# USB.net
KiCad netlist of a schematic drawn in Altium Designer
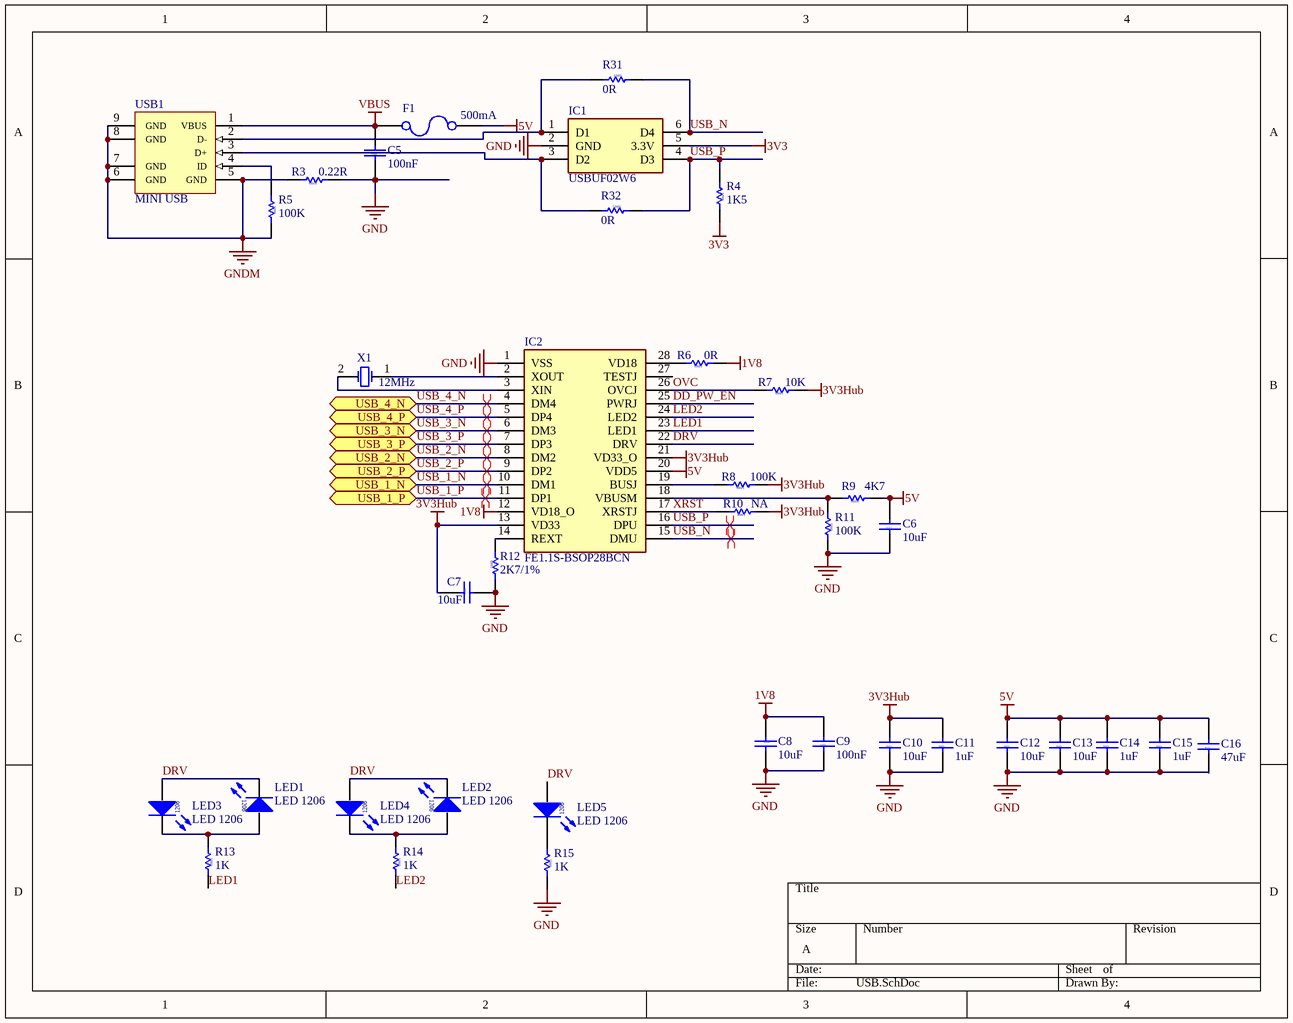
[diagram p0: USB.SchDoc]

(export (version "E")
  (design (tool "Eeschema 10.0.6"))
  (components
    (comp (ref "C5")
      (value "100nF")
      (footprint "RES 0805")
      (libsource (lib "Full lib F.kh-V2") (part "CAP 0805"))
    )
    (comp (ref "C6")
      (value "10uF")
      (footprint "Res 1206")
      (libsource (lib "Full lib F.kh-V2") (part "CAP 1206"))
    )
    (comp (ref "C7")
      (value "10uF")
      (footprint "Res 1206")
      (libsource (lib "Full lib F.kh-V2") (part "CAP 1206"))
    )
    (comp (ref "C8")
      (value "10uF")
      (footprint "Res 1206")
      (libsource (lib "Full lib F.kh-V2") (part "CAP 1206"))
    )
    (comp (ref "C9")
      (value "100nF")
      (footprint "RES 0805")
      (libsource (lib "Full lib F.kh-V2") (part "CAP 0805"))
    )
    (comp (ref "C10")
      (value "10uF")
      (footprint "Res 1206")
      (libsource (lib "Full lib F.kh-V2") (part "CAP 1206"))
    )
    (comp (ref "C11")
      (value "1uF")
      (footprint "Res 1206")
      (libsource (lib "Full lib F.kh-V2") (part "CAP 1206"))
    )
    (comp (ref "C12")
      (value "10uF")
      (footprint "Res 1206")
      (libsource (lib "Full lib F.kh-V2") (part "CAP 1206"))
    )
    (comp (ref "C13")
      (value "10uF")
      (footprint "Res 1206")
      (libsource (lib "Full lib F.kh-V2") (part "CAP 1206"))
    )
    (comp (ref "C14")
      (value "1uF")
      (footprint "Res 1206")
      (libsource (lib "Full lib F.kh-V2") (part "CAP 1206"))
    )
    (comp (ref "C15")
      (value "1uF")
      (footprint "Res 1206")
      (libsource (lib "Full lib F.kh-V2") (part "CAP 1206"))
    )
    (comp (ref "C16")
      (value "47uF")
      (footprint "Res 1206")
      (libsource (lib "Full lib F.kh-V2") (part "CAP 1206"))
    )
    (comp (ref "F1")
      (value "500mA")
      (footprint "Res 1206")
      (libsource (lib "Full lib F.kh-V2") (part "FUSE 1206"))
    )
    (comp (ref "IC1")
      (value "USBUF02W6")
      (footprint "SamacSys:SOT65P210X110-6N")
      (description "Integrated Circuit")
      (fields (field (name "MOUSER PART NUMBER") "511-USBUF02W6"))
      (libsource (lib "*") (part "USBUF02W6"))
    )
    (comp (ref "IC2")
      (value "FE1.1S-BSOP28BCN")
      (footprint "SamacSys:SOP64P600X175-28N")
      (description "Integrated Circuit")
      (libsource (lib "*") (part "FE1.1S-BSOP28BCN"))
    )
    (comp (ref "LED1")
      (value "LED 1206")
      (footprint "LED 1206")
      (libsource (lib "Full lib F.kh-V2") (part "LED 1206"))
    )
    (comp (ref "LED2")
      (value "LED 1206")
      (footprint "LED 1206")
      (libsource (lib "Full lib F.kh-V2") (part "LED 1206"))
    )
    (comp (ref "LED3")
      (value "LED 1206")
      (footprint "LED 1206")
      (libsource (lib "Full lib F.kh-V2") (part "LED 1206"))
    )
    (comp (ref "LED4")
      (value "LED 1206")
      (footprint "LED 1206")
      (libsource (lib "Full lib F.kh-V2") (part "LED 1206"))
    )
    (comp (ref "LED5")
      (value "LED 1206")
      (footprint "LED 1206")
      (libsource (lib "Full lib F.kh-V2") (part "LED 1206"))
    )
    (comp (ref "R3")
      (value "0.22R")
      (footprint "RES 0805")
      (libsource (lib "Full lib F.kh-V2") (part "RES 0805"))
    )
    (comp (ref "R4")
      (value "1K5")
      (footprint "RES 0805")
      (libsource (lib "Full lib F.kh-V2") (part "RES 0805"))
    )
    (comp (ref "R5")
      (value "100K")
      (footprint "RES 0805")
      (libsource (lib "Full lib F.kh-V2") (part "RES 0805"))
    )
    (comp (ref "R6")
      (value "0R")
      (footprint "RES 0805")
      (libsource (lib "Full lib F.kh-V2") (part "RES 0805"))
    )
    (comp (ref "R7")
      (value "10K")
      (footprint "RES 0805")
      (libsource (lib "Full lib F.kh-V2") (part "RES 0805"))
    )
    (comp (ref "R8")
      (value "100K")
      (footprint "RES 0805")
      (libsource (lib "Full lib F.kh-V2") (part "RES 0805"))
    )
    (comp (ref "R9")
      (value "4K7")
      (footprint "RES 0805")
      (libsource (lib "Full lib F.kh-V2") (part "RES 0805"))
    )
    (comp (ref "R10")
      (value "NA")
      (footprint "RES 0805")
      (description "100K")
      (libsource (lib "Full lib F.kh-V2") (part "RES 0805"))
    )
    (comp (ref "R11")
      (value "100K")
      (footprint "RES 0805")
      (libsource (lib "Full lib F.kh-V2") (part "RES 0805"))
    )
    (comp (ref "R12")
      (value "2K7/1%")
      (footprint "RES 0805")
      (libsource (lib "Full lib F.kh-V2") (part "RES 0805"))
    )
    (comp (ref "R13")
      (value "1K")
      (footprint "RES 0805")
      (libsource (lib "Full lib F.kh-V2") (part "RES 0805"))
    )
    (comp (ref "R14")
      (value "1K")
      (footprint "RES 0805")
      (libsource (lib "Full lib F.kh-V2") (part "RES 0805"))
    )
    (comp (ref "R15")
      (value "1K")
      (footprint "RES 0805")
      (libsource (lib "Full lib F.kh-V2") (part "RES 0805"))
    )
    (comp (ref "R31")
      (value "0R")
      (footprint "RES 0805")
      (libsource (lib "Full lib F.kh-V2") (part "RES 0805"))
    )
    (comp (ref "R32")
      (value "0R")
      (footprint "RES 0805")
      (libsource (lib "Full lib F.kh-V2") (part "RES 0805"))
    )
    (comp (ref "USB1")
      (value "MINI USB")
      (footprint "USB MINI DIP")
      (libsource (lib "Full lib F.kh-V2") (part "USB MINI DIP"))
    )
    (comp (ref "X1")
      (value "12MHz")
      (footprint "XTAL - SMD")
      (libsource (lib "Full lib F.kh-V2") (part "XTAL - SMD"))
    )
  )
  (nets
    (net (code "1") (name "/DD_PW_EN") (class "Default")
      (node (ref "IC2") (pin "25") (pinfunction "PWRJ_25") (pintype "passive"))
    )
    (net (code "2") (name "/DRV") (class "Default")
      (node (ref "IC2") (pin "22") (pinfunction "DRV_22") (pintype "passive"))
      (node (ref "LED1") (pin "2") (pinfunction "K_2") (pintype "passive"))
      (node (ref "LED2") (pin "2") (pinfunction "K_2") (pintype "passive"))
      (node (ref "LED3") (pin "1") (pinfunction "A_1") (pintype "passive"))
      (node (ref "LED4") (pin "1") (pinfunction "A_1") (pintype "passive"))
      (node (ref "LED5") (pin "1") (pinfunction "A_1") (pintype "passive"))
    )
    (net (code "3") (name "/LED1") (class "Default")
      (node (ref "IC2") (pin "23") (pinfunction "LED1_23") (pintype "passive"))
      (node (ref "R13") (pin "2") (pinfunction "2_2") (pintype "passive"))
    )
    (net (code "4") (name "/LED2") (class "Default")
      (node (ref "IC2") (pin "24") (pinfunction "LED2_24") (pintype "passive"))
      (node (ref "R14") (pin "2") (pinfunction "2_2") (pintype "passive"))
    )
    (net (code "5") (name "/OVC") (class "Default")
      (node (ref "IC2") (pin "26") (pinfunction "OVCJ_26") (pintype "passive"))
      (node (ref "R7") (pin "2") (pinfunction "2_2") (pintype "passive"))
    )
    (net (code "6") (name "/USB_1_N") (class "Default")
      (node (ref "IC2") (pin "10") (pinfunction "DM1_10") (pintype "passive"))
    )
    (net (code "7") (name "/USB_1_P") (class "Default")
      (node (ref "IC2") (pin "11") (pinfunction "DP1_11") (pintype "passive"))
    )
    (net (code "8") (name "/USB_2_N") (class "Default")
      (node (ref "IC2") (pin "8") (pinfunction "DM2_8") (pintype "passive"))
    )
    (net (code "9") (name "/USB_2_P") (class "Default")
      (node (ref "IC2") (pin "9") (pinfunction "DP2_9") (pintype "passive"))
    )
    (net (code "10") (name "/USB_3_N") (class "Default")
      (node (ref "IC2") (pin "6") (pinfunction "DM3_6") (pintype "passive"))
    )
    (net (code "11") (name "/USB_3_P") (class "Default")
      (node (ref "IC2") (pin "7") (pinfunction "DP3_7") (pintype "passive"))
    )
    (net (code "12") (name "/USB_4_N") (class "Default")
      (node (ref "IC2") (pin "4") (pinfunction "DM4_4") (pintype "passive"))
    )
    (net (code "13") (name "/USB_4_P") (class "Default")
      (node (ref "IC2") (pin "5") (pinfunction "DP4_5") (pintype "passive"))
    )
    (net (code "14") (name "/USB_N") (class "Default")
      (node (ref "IC1") (pin "6") (pinfunction "D4_6") (pintype "passive"))
      (node (ref "IC2") (pin "15") (pinfunction "DMU_15") (pintype "passive"))
      (node (ref "R31") (pin "2") (pinfunction "2_2") (pintype "passive"))
    )
    (net (code "15") (name "/USB_P") (class "Default")
      (node (ref "IC1") (pin "4") (pinfunction "D3_4") (pintype "passive"))
      (node (ref "IC2") (pin "16") (pinfunction "DPU_16") (pintype "passive"))
      (node (ref "R32") (pin "2") (pinfunction "2_2") (pintype "passive"))
      (node (ref "R4") (pin "1") (pinfunction "1_1") (pintype "passive"))
    )
    (net (code "16") (name "/XRST") (class "Default")
      (node (ref "IC2") (pin "17") (pinfunction "XRSTJ_17") (pintype "passive"))
      (node (ref "R10") (pin "2") (pinfunction "2_2") (pintype "passive"))
    )
    (net (code "17") (name "1V8") (class "Default")
      (node (ref "C8") (pin "1") (pinfunction "1_1") (pintype "passive"))
      (node (ref "C9") (pin "2") (pinfunction "2_2") (pintype "passive"))
      (node (ref "IC2") (pin "12") (pinfunction "VD18_O_12") (pintype "passive"))
      (node (ref "R6") (pin "1") (pinfunction "1_1") (pintype "passive"))
    )
    (net (code "18") (name "3V3") (class "Default")
      (node (ref "IC1") (pin "5") (pinfunction "3.3V_5") (pintype "passive"))
      (node (ref "R4") (pin "2") (pinfunction "2_2") (pintype "passive"))
    )
    (net (code "19") (name "3V3Hub") (class "Default")
      (node (ref "C10") (pin "2") (pinfunction "2_2") (pintype "passive"))
      (node (ref "C11") (pin "2") (pinfunction "2_2") (pintype "passive"))
      (node (ref "C7") (pin "1") (pinfunction "1_1") (pintype "passive"))
      (node (ref "IC2") (pin "13") (pinfunction "VD33_13") (pintype "passive"))
      (node (ref "IC2") (pin "21") (pinfunction "VD33_O_21") (pintype "passive"))
      (node (ref "R10") (pin "1") (pinfunction "1_1") (pintype "passive"))
      (node (ref "R7") (pin "1") (pinfunction "1_1") (pintype "passive"))
      (node (ref "R8") (pin "1") (pinfunction "1_1") (pintype "passive"))
    )
    (net (code "20") (name "5V") (class "Default")
      (node (ref "C12") (pin "2") (pinfunction "2_2") (pintype "passive"))
      (node (ref "C13") (pin "2") (pinfunction "2_2") (pintype "passive"))
      (node (ref "C14") (pin "2") (pinfunction "2_2") (pintype "passive"))
      (node (ref "C15") (pin "2") (pinfunction "2_2") (pintype "passive"))
      (node (ref "C16") (pin "2") (pinfunction "2_2") (pintype "passive"))
      (node (ref "C6") (pin "2") (pinfunction "2_2") (pintype "passive"))
      (node (ref "F1") (pin "2") (pinfunction "2_2") (pintype "passive"))
      (node (ref "IC2") (pin "20") (pinfunction "VDD5_20") (pintype "passive"))
      (node (ref "R9") (pin "1") (pinfunction "1_1") (pintype "passive"))
    )
    (net (code "21") (name "GND") (class "Default")
      (node (ref "C10") (pin "1") (pinfunction "1_1") (pintype "passive"))
      (node (ref "C11") (pin "1") (pinfunction "1_1") (pintype "passive"))
      (node (ref "C12") (pin "1") (pinfunction "1_1") (pintype "passive"))
      (node (ref "C13") (pin "1") (pinfunction "1_1") (pintype "passive"))
      (node (ref "C14") (pin "1") (pinfunction "1_1") (pintype "passive"))
      (node (ref "C15") (pin "1") (pinfunction "1_1") (pintype "passive"))
      (node (ref "C16") (pin "1") (pinfunction "1_1") (pintype "passive"))
      (node (ref "C5") (pin "1") (pinfunction "1_1") (pintype "passive"))
      (node (ref "C6") (pin "1") (pinfunction "1_1") (pintype "passive"))
      (node (ref "C7") (pin "2") (pinfunction "2_2") (pintype "passive"))
      (node (ref "C8") (pin "2") (pinfunction "2_2") (pintype "passive"))
      (node (ref "C9") (pin "1") (pinfunction "1_1") (pintype "passive"))
      (node (ref "IC1") (pin "2") (pinfunction "GND_2") (pintype "power_in"))
      (node (ref "IC2") (pin "1") (pinfunction "VSS_1") (pintype "passive"))
      (node (ref "R11") (pin "2") (pinfunction "2_2") (pintype "passive"))
      (node (ref "R12") (pin "1") (pinfunction "1_1") (pintype "passive"))
      (node (ref "R15") (pin "2") (pinfunction "2_2") (pintype "passive"))
      (node (ref "R3") (pin "1") (pinfunction "1_1") (pintype "passive"))
    )
    (net (code "22") (name "GNDM") (class "Default")
      (node (ref "R3") (pin "2") (pinfunction "2_2") (pintype "passive"))
      (node (ref "R5") (pin "2") (pinfunction "2_2") (pintype "passive"))
      (node (ref "USB1") (pin "5") (pinfunction "GND_5") (pintype "power_in"))
      (node (ref "USB1") (pin "6") (pinfunction "GND_6") (pintype "passive"))
      (node (ref "USB1") (pin "7") (pinfunction "GND_7") (pintype "passive"))
      (node (ref "USB1") (pin "8") (pinfunction "GND_8") (pintype "passive"))
      (node (ref "USB1") (pin "9") (pinfunction "GND_9") (pintype "passive"))
    )
    (net (code "23") (name "Net-(IC1-D1)") (class "Default")
      (node (ref "IC1") (pin "1") (pinfunction "D1_1") (pintype "passive"))
      (node (ref "R31") (pin "1") (pinfunction "1_1") (pintype "passive"))
      (node (ref "USB1") (pin "2") (pinfunction "D-_2") (pintype "input"))
    )
    (net (code "24") (name "Net-(IC1-D2)") (class "Default")
      (node (ref "IC1") (pin "3") (pinfunction "D2_3") (pintype "passive"))
      (node (ref "R32") (pin "1") (pinfunction "1_1") (pintype "passive"))
      (node (ref "USB1") (pin "3") (pinfunction "D+_3") (pintype "input"))
    )
    (net (code "25") (name "Net-(IC2-BUSJ)") (class "Default")
      (node (ref "IC2") (pin "19") (pinfunction "BUSJ_19") (pintype "passive"))
      (node (ref "R8") (pin "2") (pinfunction "2_2") (pintype "passive"))
    )
    (net (code "26") (name "Net-(IC2-REXT)") (class "Default")
      (node (ref "IC2") (pin "14") (pinfunction "REXT_14") (pintype "passive"))
      (node (ref "R12") (pin "2") (pinfunction "2_2") (pintype "passive"))
    )
    (net (code "27") (name "Net-(IC2-VBUSM)") (class "Default")
      (node (ref "IC2") (pin "18") (pinfunction "VBUSM_18") (pintype "passive"))
      (node (ref "R11") (pin "1") (pinfunction "1_1") (pintype "passive"))
      (node (ref "R9") (pin "2") (pinfunction "2_2") (pintype "passive"))
    )
    (net (code "28") (name "Net-(IC2-VD18)") (class "Default")
      (node (ref "IC2") (pin "28") (pinfunction "VD18_28") (pintype "passive"))
      (node (ref "R6") (pin "2") (pinfunction "2_2") (pintype "passive"))
    )
    (net (code "29") (name "Net-(IC2-XIN)") (class "Default")
      (node (ref "IC2") (pin "3") (pinfunction "XIN_3") (pintype "passive"))
      (node (ref "X1") (pin "2") (pinfunction "OSC2_2") (pintype "passive"))
    )
    (net (code "30") (name "Net-(IC2-XOUT)") (class "Default")
      (node (ref "IC2") (pin "2") (pinfunction "XOUT_2") (pintype "passive"))
      (node (ref "X1") (pin "1") (pinfunction "OSC1_1") (pintype "passive"))
    )
    (net (code "31") (name "Net-(LED1-A)") (class "Default")
      (node (ref "LED1") (pin "1") (pinfunction "A_1") (pintype "passive"))
      (node (ref "LED3") (pin "2") (pinfunction "K_2") (pintype "passive"))
      (node (ref "R13") (pin "1") (pinfunction "1_1") (pintype "passive"))
    )
    (net (code "32") (name "Net-(LED2-A)") (class "Default")
      (node (ref "LED2") (pin "1") (pinfunction "A_1") (pintype "passive"))
      (node (ref "LED4") (pin "2") (pinfunction "K_2") (pintype "passive"))
      (node (ref "R14") (pin "1") (pinfunction "1_1") (pintype "passive"))
    )
    (net (code "33") (name "Net-(LED5-K)") (class "Default")
      (node (ref "LED5") (pin "2") (pinfunction "K_2") (pintype "passive"))
      (node (ref "R15") (pin "1") (pinfunction "1_1") (pintype "passive"))
    )
    (net (code "34") (name "Net-(USB1-ID)") (class "Default")
      (node (ref "R5") (pin "1") (pinfunction "1_1") (pintype "passive"))
      (node (ref "USB1") (pin "4") (pinfunction "ID_4") (pintype "input"))
    )
    (net (code "35") (name "VBUS") (class "Default")
      (node (ref "C5") (pin "2") (pinfunction "2_2") (pintype "passive"))
      (node (ref "F1") (pin "1") (pinfunction "1_1") (pintype "passive"))
      (node (ref "USB1") (pin "1") (pinfunction "VBUS_1") (pintype "power_in"))
    )
    (net (code "36") (name "unconnected-(IC2-TESTJ-Pad27)") (class "Default")
      (node (ref "IC2") (pin "27") (pinfunction "TESTJ_27") (pintype "passive"))
    )
  )
)
